# Printing6.net
KiCad netlist of a schematic drawn in Altium Designer
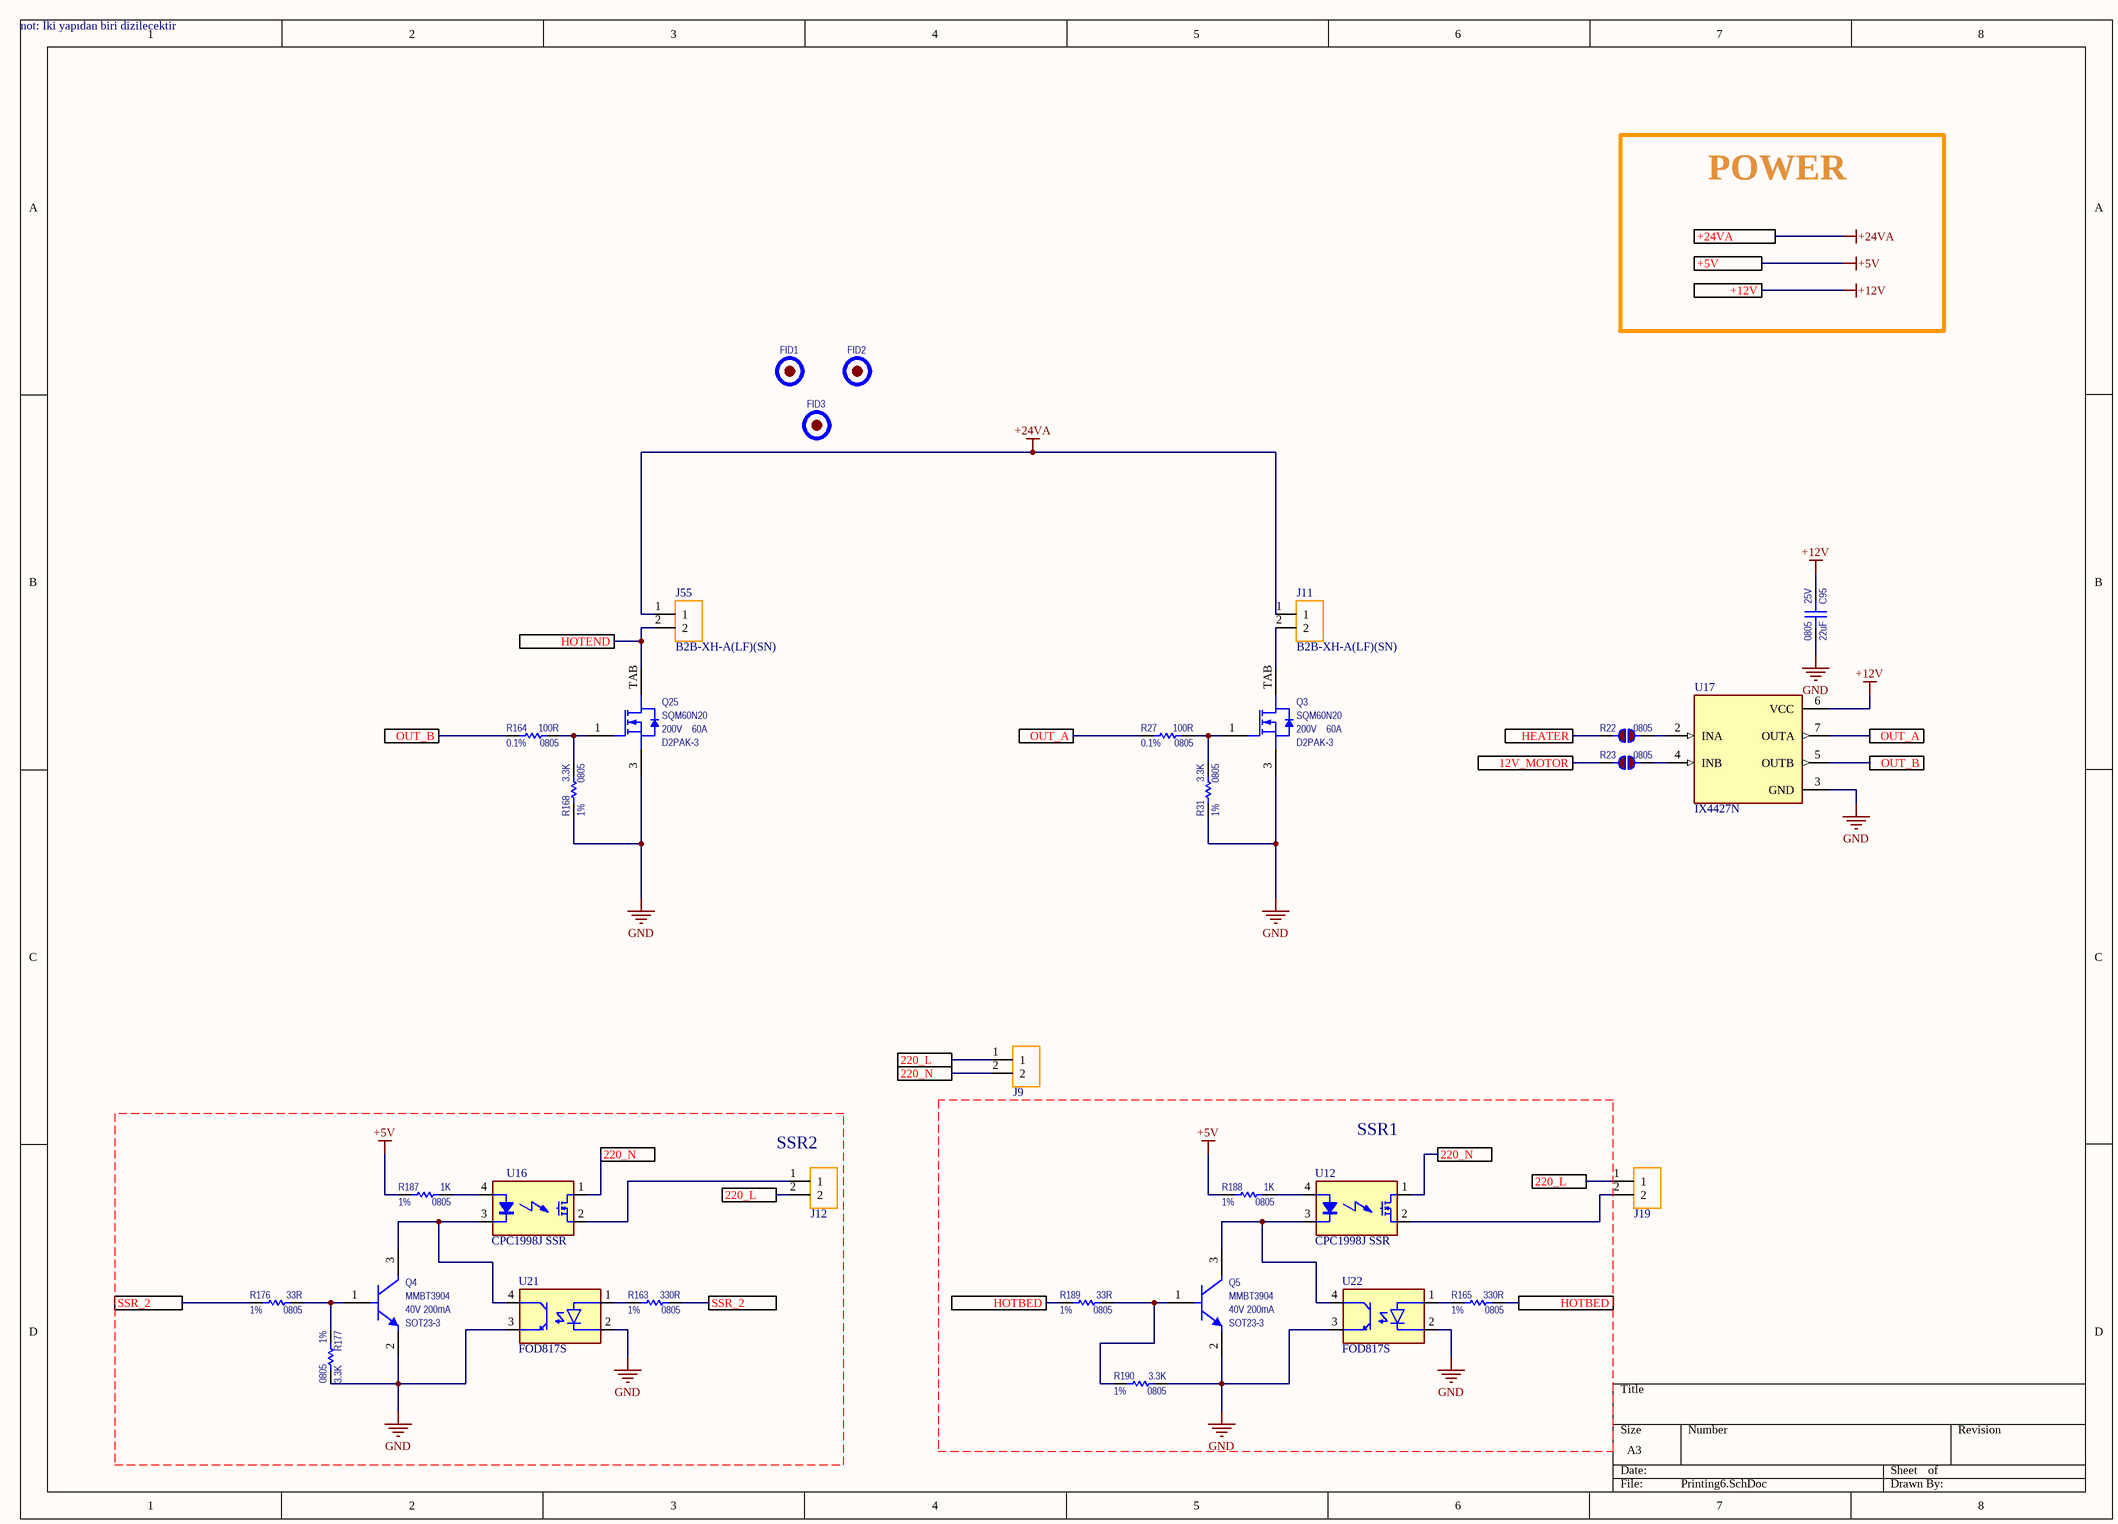
[diagram p0: Printing6.SchDoc]

(export (version "E")
  (design (tool "Eeschema 10.0.6"))
  (components
    (comp (ref "C95")
      (value "22uF")
      (footprint "C_0805_GEN_1.40H")
      (description "CAP_CER_22uF_25V_X5R_20%_0805")
      (fields
        (field (name "VOLTAGE") "25V")
        (field (name "PACKAGE") "0805")
        (field (name "SIMILAR PART") "GRT21BR61E226ME13L; C2012X5R1V226M125AC")
        (field (name "TOLERANCE") "20%")
        (field (name "ADDED BY") "HasanA")
        (field (name "CHECKED BY") "İlkerU")
      )
      (libsource (lib "FireANTs_HwLibDB") (part "Capacitor"))
    )
    (comp (ref "FID1")
      (value "Fiducial_1.00x3.00")
      (footprint "SMD_1.00x3.00_FID")
      (description "SUP_FID_1.00x3.00_SMD")
      (fields
        (field (name "SIMILAR PART") "X")
        (field (name "ADDED BY") "İlhanT")
        (field (name "CHECKED BY") "HasanA")
      )
      (libsource (lib "FireANTs_HwLibDB") (part "Fiducial_1.00x3.00"))
    )
    (comp (ref "FID2")
      (value "Fiducial_1.00x3.00")
      (footprint "SMD_1.00x3.00_FID")
      (description "SUP_FID_1.00x3.00_SMD")
      (fields
        (field (name "SIMILAR PART") "X")
        (field (name "ADDED BY") "İlhanT")
        (field (name "CHECKED BY") "HasanA")
      )
      (libsource (lib "FireANTs_HwLibDB") (part "Fiducial_1.00x3.00"))
    )
    (comp (ref "FID3")
      (value "Fiducial_1.00x3.00")
      (footprint "SMD_1.00x3.00_FID")
      (description "SUP_FID_1.00x3.00_SMD")
      (fields
        (field (name "SIMILAR PART") "X")
        (field (name "ADDED BY") "İlhanT")
        (field (name "CHECKED BY") "HasanA")
      )
      (libsource (lib "FireANTs_HwLibDB") (part "Fiducial_1.00x3.00"))
    )
    (comp (ref "J9")
      (value "5.08 Klemens")
      (footprint "5.08 Klemens")
      (libsource (lib "Printing") (part "5.08 Klemens"))
    )
    (comp (ref "J11")
      (value "B2B-XH-A(LF)(SN)")
      (footprint "JST_B2B-XH-A(LF)(SN)")
      (description "Connector Header Through Hole 2 position 0.098 (2.50mm)")
      (fields (field (name "MF") "JST Sales"))
      (libsource (lib "Printing") (part "B2B-XH-A(LF)(SN)"))
    )
    (comp (ref "J12")
      (value "5.08 Klemens")
      (footprint "5.08 Klemens")
      (libsource (lib "Printing") (part "5.08 Klemens"))
    )
    (comp (ref "J19")
      (value "5.08 Klemens")
      (footprint "5.08 Klemens")
      (libsource (lib "Printing") (part "5.08 Klemens"))
    )
    (comp (ref "J55")
      (value "B2B-XH-A(LF)(SN)")
      (footprint "JST_B2B-XH-A(LF)(SN)")
      (description "Connector Header Through Hole 2 position 0.098 (2.50mm)")
      (fields (field (name "MF") "JST Sales"))
      (libsource (lib "Printing") (part "B2B-XH-A(LF)(SN)"))
    )
    (comp (ref "Q3")
      (value "SQM60N20")
      (footprint "D2PAK-3_SQM60N20-35")
      (description "TRA_NMOS_SING_200V_60A_TH3V_DPAK")
      (fields
        (field (name "CURRENT") "60A")
        (field (name "VOLTAGE") "200V")
        (field (name "PACKAGE") "D2PAK-3")
        (field (name "SIMILAR PART") "SQM10250E_GE3")
        (field (name "TOLERANCE") "X")
        (field (name "ADDED BY") "İlhanT")
        (field (name "CHECKED BY") "EserC")
      )
      (libsource (lib "FireANTs_HwLibDB") (part "SingleNMOS_G1S3DTAB"))
    )
    (comp (ref "Q4")
      (value "MMBT3904")
      (footprint "SOT23-3_MMBT3904,215")
      (description "TRA_NPN_SING_40V_200mA_VSAT300mV_SOT23-3")
      (fields
        (field (name "CURRENT") "200mA")
        (field (name "VOLTAGE") "40V")
        (field (name "PACKAGE") "SOT23-3")
        (field (name "SIMILAR PART") "SST3904HZGT116; PMBT3904,235")
        (field (name "TOLERANCE") "X")
        (field (name "ADDED BY") "HasanA")
        (field (name "CHECKED BY") "EserC")
      )
      (libsource (lib "FireANTs_HwLibDB") (part "SingleNPN_B1E2C3"))
    )
    (comp (ref "Q5")
      (value "MMBT3904")
      (footprint "SOT23-3_MMBT3904,215")
      (description "TRA_NPN_SING_40V_200mA_VSAT300mV_SOT23-3")
      (fields
        (field (name "CURRENT") "200mA")
        (field (name "VOLTAGE") "40V")
        (field (name "PACKAGE") "SOT23-3")
        (field (name "SIMILAR PART") "SST3904HZGT116; PMBT3904,235")
        (field (name "TOLERANCE") "X")
        (field (name "ADDED BY") "HasanA")
        (field (name "CHECKED BY") "EserC")
      )
      (libsource (lib "FireANTs_HwLibDB") (part "SingleNPN_B1E2C3"))
    )
    (comp (ref "Q25")
      (value "SQM60N20")
      (footprint "D2PAK-3_SQM60N20-35")
      (description "TRA_NMOS_SING_200V_60A_TH3V_DPAK")
      (fields
        (field (name "CURRENT") "60A")
        (field (name "VOLTAGE") "200V")
        (field (name "PACKAGE") "D2PAK-3")
        (field (name "SIMILAR PART") "SQM10250E_GE3")
        (field (name "TOLERANCE") "X")
        (field (name "ADDED BY") "İlhanT")
        (field (name "CHECKED BY") "EserC")
      )
      (libsource (lib "FireANTs_HwLibDB") (part "SingleNMOS_G1S3DTAB"))
    )
    (comp (ref "R22")
      (value "StandardJumper")
      (footprint "R_0805_GEN_0.70H")
      (description "RES_STD_0R_0.125W_0805")
      (fields
        (field (name "PACKAGE") "0805")
        (field (name "TOLERANCE") "5%")
        (field (name "VOLTAGE") "150V")
        (field (name "ADDED BY") "İlhanT")
        (field (name "CHECKED BY") "YasinY")
      )
      (libsource (lib "FireANTs_HwLibDB") (part "StandardJumper"))
    )
    (comp (ref "R23")
      (value "StandardJumper")
      (footprint "R_0805_GEN_0.70H")
      (description "RES_STD_0R_0.125W_0805")
      (fields
        (field (name "PACKAGE") "0805")
        (field (name "TOLERANCE") "5%")
        (field (name "VOLTAGE") "150V")
        (field (name "ADDED BY") "İlhanT")
        (field (name "CHECKED BY") "YasinY")
      )
      (libsource (lib "FireANTs_HwLibDB") (part "StandardJumper"))
    )
    (comp (ref "R27")
      (value "100R")
      (footprint "R_0805_GEN_0.70H")
      (description "RES_STD_100R_0.125W_0.1%_10ppm_0805")
      (fields
        (field (name "TOLERANCE") "0.1%")
        (field (name "PACKAGE") "0805")
        (field (name "SIMILAR PART") "RNCF0805TKY100R; RG2012N-101-W-T1")
        (field (name "VOLTAGE") "150V")
        (field (name "ADDED BY") "HasanA")
        (field (name "CHECKED BY") "YasinY")
      )
      (libsource (lib "FireANTs_HwLibDB") (part "StandardResistor"))
    )
    (comp (ref "R31")
      (value "3.3K")
      (footprint "R_0805_GEN_0.70H")
      (description "RES_STD_3.3K_0.125W_1%_100ppm_0805")
      (fields
        (field (name "TOLERANCE") "1%")
        (field (name "PACKAGE") "0805")
        (field (name "VOLTAGE") "150V")
        (field (name "Comment") "StandardResistor")
        (field (name "ADDED BY") "HasanA")
        (field (name "CHECKED BY") "YasinY")
      )
      (libsource (lib "FireANTs_HwLibDB") (part "StandardResistor"))
    )
    (comp (ref "R163")
      (value "330R")
      (footprint "R_0805_GEN_0.70H")
      (description "RES_STD_33R_0.125W_1%_100ppm_0805")
      (fields
        (field (name "TOLERANCE") "1%")
        (field (name "PACKAGE") "0805")
        (field (name "VOLTAGE") "150V")
        (field (name "Comment") "StandardResistor")
        (field (name "ADDED BY") "HasanA")
        (field (name "CHECKED BY") "YasinY")
      )
      (libsource (lib "FireANTs_HwLibDB") (part "StandardResistor"))
    )
    (comp (ref "R164")
      (value "100R")
      (footprint "R_0805_GEN_0.70H")
      (description "RES_STD_100R_0.125W_0.1%_10ppm_0805")
      (fields
        (field (name "TOLERANCE") "0.1%")
        (field (name "PACKAGE") "0805")
        (field (name "SIMILAR PART") "RNCF0805TKY100R; RG2012N-101-W-T1")
        (field (name "VOLTAGE") "150V")
        (field (name "ADDED BY") "HasanA")
        (field (name "CHECKED BY") "YasinY")
      )
      (libsource (lib "FireANTs_HwLibDB") (part "StandardResistor"))
    )
    (comp (ref "R165")
      (value "330R")
      (footprint "R_0805_GEN_0.70H")
      (description "RES_STD_33R_0.125W_1%_100ppm_0805")
      (fields
        (field (name "TOLERANCE") "1%")
        (field (name "PACKAGE") "0805")
        (field (name "VOLTAGE") "150V")
        (field (name "Comment") "StandardResistor")
        (field (name "ADDED BY") "HasanA")
        (field (name "CHECKED BY") "YasinY")
      )
      (libsource (lib "FireANTs_HwLibDB") (part "StandardResistor"))
    )
    (comp (ref "R168")
      (value "3.3K")
      (footprint "R_0805_GEN_0.70H")
      (description "RES_STD_3.3K_0.125W_1%_100ppm_0805")
      (fields
        (field (name "TOLERANCE") "1%")
        (field (name "PACKAGE") "0805")
        (field (name "VOLTAGE") "150V")
        (field (name "Comment") "StandardResistor")
        (field (name "ADDED BY") "HasanA")
        (field (name "CHECKED BY") "YasinY")
      )
      (libsource (lib "FireANTs_HwLibDB") (part "StandardResistor"))
    )
    (comp (ref "R176")
      (value "33R")
      (footprint "R_0805_GEN_0.70H")
      (description "RES_STD_33R_0.125W_1%_100ppm_0805")
      (fields
        (field (name "TOLERANCE") "1%")
        (field (name "PACKAGE") "0805")
        (field (name "VOLTAGE") "150V")
        (field (name "Comment") "StandardResistor")
        (field (name "ADDED BY") "HasanA")
        (field (name "CHECKED BY") "YasinY")
      )
      (libsource (lib "FireANTs_HwLibDB") (part "StandardResistor"))
    )
    (comp (ref "R177")
      (value "3.3K")
      (footprint "R_0805_GEN_0.70H")
      (description "RES_STD_3.3K_0.125W_1%_100ppm_0805")
      (fields
        (field (name "TOLERANCE") "1%")
        (field (name "PACKAGE") "0805")
        (field (name "VOLTAGE") "150V")
        (field (name "Comment") "StandardResistor")
        (field (name "ADDED BY") "HasanA")
        (field (name "CHECKED BY") "YasinY")
      )
      (libsource (lib "FireANTs_HwLibDB") (part "StandardResistor"))
    )
    (comp (ref "R187")
      (value "1K")
      (footprint "R_0805_GEN_0.70H")
      (description "RES_STD_3.3K_0.125W_1%_100ppm_0805")
      (fields
        (field (name "TOLERANCE") "1%")
        (field (name "PACKAGE") "0805")
        (field (name "VOLTAGE") "150V")
        (field (name "Comment") "StandardResistor")
        (field (name "ADDED BY") "HasanA")
        (field (name "CHECKED BY") "YasinY")
      )
      (libsource (lib "FireANTs_HwLibDB") (part "StandardResistor"))
    )
    (comp (ref "R188")
      (value "1K")
      (footprint "R_0805_GEN_0.70H")
      (description "RES_STD_3.3K_0.125W_1%_100ppm_0805")
      (fields
        (field (name "TOLERANCE") "1%")
        (field (name "PACKAGE") "0805")
        (field (name "VOLTAGE") "150V")
        (field (name "Comment") "StandardResistor")
        (field (name "ADDED BY") "HasanA")
        (field (name "CHECKED BY") "YasinY")
      )
      (libsource (lib "FireANTs_HwLibDB") (part "StandardResistor"))
    )
    (comp (ref "R189")
      (value "33R")
      (footprint "R_0805_GEN_0.70H")
      (description "RES_STD_33R_0.125W_1%_100ppm_0805")
      (fields
        (field (name "TOLERANCE") "1%")
        (field (name "PACKAGE") "0805")
        (field (name "VOLTAGE") "150V")
        (field (name "Comment") "StandardResistor")
        (field (name "ADDED BY") "HasanA")
        (field (name "CHECKED BY") "YasinY")
      )
      (libsource (lib "FireANTs_HwLibDB") (part "StandardResistor"))
    )
    (comp (ref "R190")
      (value "3.3K")
      (footprint "R_0805_GEN_0.70H")
      (description "RES_STD_3.3K_0.125W_1%_100ppm_0805")
      (fields
        (field (name "TOLERANCE") "1%")
        (field (name "PACKAGE") "0805")
        (field (name "VOLTAGE") "150V")
        (field (name "Comment") "StandardResistor")
        (field (name "ADDED BY") "HasanA")
        (field (name "CHECKED BY") "YasinY")
      )
      (libsource (lib "FireANTs_HwLibDB") (part "StandardResistor"))
    )
    (comp (ref "U12")
      (value "CPC1998J SSR")
      (footprint "I4-PAC")
      (libsource (lib "Printing") (part "CPC1998J"))
    )
    (comp (ref "U16")
      (value "CPC1998J SSR")
      (footprint "I4-PAC")
      (libsource (lib "Printing") (part "CPC1998J"))
    )
    (comp (ref "U17")
      (value "IX4427N")
      (footprint "SOIC127P600X175-8N")
      (description "Low-Side Gate Driver IC Non-Inverting 8-SOIC")
      (fields (field (name "MF") "IXYS Integrated"))
      (libsource (lib "Printing") (part "IX4427N"))
    )
    (comp (ref "U21")
      (value "FOD817S")
      (footprint "SOIC254P1016X385-4N")
      (description "Optoisolator Transistor Output 5000Vrms 1 Channel 4-SMD")
      (fields (field (name "MF") "ON Semiconductor"))
      (libsource (lib "Printing") (part "FOD817S"))
    )
    (comp (ref "U22")
      (value "FOD817S")
      (footprint "SOIC254P1016X385-4N")
      (description "Optoisolator Transistor Output 5000Vrms 1 Channel 4-SMD")
      (fields (field (name "MF") "ON Semiconductor"))
      (libsource (lib "Printing") (part "FOD817S"))
    )
  )
  (nets
    (net (code "1") (name "+5V") (class "Default")
      (node (ref "R187") (pin "1") (pinfunction "1_1") (pintype "passive"))
      (node (ref "R188") (pin "1") (pinfunction "1_1") (pintype "passive"))
    )
    (net (code "2") (name "+12V") (class "Default")
      (node (ref "C95") (pin "1") (pinfunction "1_1") (pintype "passive"))
      (node (ref "U17") (pin "6") (pinfunction "VCC_6") (pintype "power_in"))
    )
    (net (code "3") (name "+24VA") (class "Default")
      (node (ref "J11") (pin "1") (pinfunction "1_1") (pintype "passive"))
      (node (ref "J55") (pin "1") (pinfunction "1_1") (pintype "passive"))
    )
    (net (code "4") (name "/12V_MOTOR") (class "Default")
      (node (ref "R23") (pin "1") (pinfunction "1_1") (pintype "passive"))
    )
    (net (code "5") (name "/220_L") (class "Default")
      (node (ref "J12") (pin "2") (pinfunction "2_2") (pintype "passive"))
      (node (ref "J19") (pin "1") (pinfunction "1_1") (pintype "passive"))
      (node (ref "J9") (pin "1") (pinfunction "1_1") (pintype "passive"))
    )
    (net (code "6") (name "/220_N") (class "Default")
      (node (ref "J9") (pin "2") (pinfunction "2_2") (pintype "passive"))
      (node (ref "U12") (pin "1") (pinfunction "DS1_1") (pintype "passive"))
      (node (ref "U16") (pin "1") (pinfunction "DS1_1") (pintype "passive"))
    )
    (net (code "7") (name "/HEATER") (class "Default")
      (node (ref "R22") (pin "1") (pinfunction "1_1") (pintype "passive"))
    )
    (net (code "8") (name "/HOTBED") (class "Default")
      (node (ref "R165") (pin "2") (pinfunction "2_2") (pintype "passive"))
      (node (ref "R189") (pin "1") (pinfunction "1_1") (pintype "passive"))
    )
    (net (code "9") (name "/HOTEND") (class "Default")
      (node (ref "J55") (pin "2") (pinfunction "2_2") (pintype "passive"))
      (node (ref "Q25") (pin "TAB") (pinfunction "DRAIN_TAB") (pintype "passive"))
    )
    (net (code "10") (name "/OUT_A") (class "Default")
      (node (ref "R27") (pin "1") (pinfunction "1_1") (pintype "passive"))
      (node (ref "U17") (pin "7") (pinfunction "OUTA_7") (pintype "output"))
    )
    (net (code "11") (name "/OUT_B") (class "Default")
      (node (ref "R164") (pin "1") (pinfunction "1_1") (pintype "passive"))
      (node (ref "U17") (pin "5") (pinfunction "OUTB_5") (pintype "output"))
    )
    (net (code "12") (name "/SSR_2") (class "Default")
      (node (ref "R163") (pin "2") (pinfunction "2_2") (pintype "passive"))
      (node (ref "R176") (pin "1") (pinfunction "1_1") (pintype "passive"))
    )
    (net (code "13") (name "GND") (class "Default")
      (node (ref "C95") (pin "2") (pinfunction "2_2") (pintype "passive"))
      (node (ref "Q25") (pin "3") (pinfunction "SOURCE_3") (pintype "passive"))
      (node (ref "Q3") (pin "3") (pinfunction "SOURCE_3") (pintype "passive"))
      (node (ref "Q4") (pin "2") (pinfunction "EMITTER_2") (pintype "passive"))
      (node (ref "Q5") (pin "2") (pinfunction "EMITTER_2") (pintype "passive"))
      (node (ref "R168") (pin "1") (pinfunction "1_1") (pintype "passive"))
      (node (ref "R177") (pin "2") (pinfunction "2_2") (pintype "passive"))
      (node (ref "R190") (pin "2") (pinfunction "2_2") (pintype "passive"))
      (node (ref "R31") (pin "1") (pinfunction "1_1") (pintype "passive"))
      (node (ref "U17") (pin "3") (pinfunction "GND_3") (pintype "power_in"))
      (node (ref "U21") (pin "2") (pinfunction "CATHODE_2") (pintype "passive"))
      (node (ref "U21") (pin "3") (pinfunction "EMITTER_3") (pintype "passive"))
      (node (ref "U22") (pin "2") (pinfunction "CATHODE_2") (pintype "passive"))
      (node (ref "U22") (pin "3") (pinfunction "EMITTER_3") (pintype "passive"))
    )
    (net (code "14") (name "Net-(Q3-DRAIN)") (class "Default")
      (node (ref "J11") (pin "2") (pinfunction "2_2") (pintype "passive"))
      (node (ref "Q3") (pin "TAB") (pinfunction "DRAIN_TAB") (pintype "passive"))
    )
    (net (code "15") (name "Net-(Q3-GATE)") (class "Default")
      (node (ref "Q3") (pin "1") (pinfunction "GATE_1") (pintype "passive"))
      (node (ref "R27") (pin "2") (pinfunction "2_2") (pintype "passive"))
      (node (ref "R31") (pin "2") (pinfunction "2_2") (pintype "passive"))
    )
    (net (code "16") (name "Net-(Q4-BASE)") (class "Default")
      (node (ref "Q4") (pin "1") (pinfunction "BASE_1") (pintype "passive"))
      (node (ref "R176") (pin "2") (pinfunction "2_2") (pintype "passive"))
      (node (ref "R177") (pin "1") (pinfunction "1_1") (pintype "passive"))
    )
    (net (code "17") (name "Net-(Q4-COLLECTOR)") (class "Default")
      (node (ref "Q4") (pin "3") (pinfunction "COLLECTOR_3") (pintype "passive"))
      (node (ref "U16") (pin "3") (pinfunction "K_3") (pintype "passive"))
      (node (ref "U21") (pin "4") (pinfunction "COLLECTOR_4") (pintype "passive"))
    )
    (net (code "18") (name "Net-(Q5-BASE)") (class "Default")
      (node (ref "Q5") (pin "1") (pinfunction "BASE_1") (pintype "passive"))
      (node (ref "R189") (pin "2") (pinfunction "2_2") (pintype "passive"))
      (node (ref "R190") (pin "1") (pinfunction "1_1") (pintype "passive"))
    )
    (net (code "19") (name "Net-(Q5-COLLECTOR)") (class "Default")
      (node (ref "Q5") (pin "3") (pinfunction "COLLECTOR_3") (pintype "passive"))
      (node (ref "U12") (pin "3") (pinfunction "K_3") (pintype "passive"))
      (node (ref "U22") (pin "4") (pinfunction "COLLECTOR_4") (pintype "passive"))
    )
    (net (code "20") (name "Net-(Q25-GATE)") (class "Default")
      (node (ref "Q25") (pin "1") (pinfunction "GATE_1") (pintype "passive"))
      (node (ref "R164") (pin "2") (pinfunction "2_2") (pintype "passive"))
      (node (ref "R168") (pin "2") (pinfunction "2_2") (pintype "passive"))
    )
    (net (code "21") (name "Net-(U12-A)") (class "Default")
      (node (ref "R188") (pin "2") (pinfunction "2_2") (pintype "passive"))
      (node (ref "U12") (pin "4") (pinfunction "A_4") (pintype "passive"))
    )
    (net (code "22") (name "Net-(U12-DS2)") (class "Default")
      (node (ref "J19") (pin "2") (pinfunction "2_2") (pintype "passive"))
      (node (ref "U12") (pin "2") (pinfunction "DS2_2") (pintype "passive"))
    )
    (net (code "23") (name "Net-(U16-A)") (class "Default")
      (node (ref "R187") (pin "2") (pinfunction "2_2") (pintype "passive"))
      (node (ref "U16") (pin "4") (pinfunction "A_4") (pintype "passive"))
    )
    (net (code "24") (name "Net-(U16-DS2)") (class "Default")
      (node (ref "J12") (pin "1") (pinfunction "1_1") (pintype "passive"))
      (node (ref "U16") (pin "2") (pinfunction "DS2_2") (pintype "passive"))
    )
    (net (code "25") (name "Net-(U17-INA)") (class "Default")
      (node (ref "R22") (pin "2") (pinfunction "2_2") (pintype "passive"))
      (node (ref "U17") (pin "2") (pinfunction "INA_2") (pintype "input"))
    )
    (net (code "26") (name "Net-(U17-INB)") (class "Default")
      (node (ref "R23") (pin "2") (pinfunction "2_2") (pintype "passive"))
      (node (ref "U17") (pin "4") (pinfunction "INB_4") (pintype "input"))
    )
    (net (code "27") (name "Net-(U21-ANODE)") (class "Default")
      (node (ref "R163") (pin "1") (pinfunction "1_1") (pintype "passive"))
      (node (ref "U21") (pin "1") (pinfunction "ANODE_1") (pintype "passive"))
    )
    (net (code "28") (name "Net-(U22-ANODE)") (class "Default")
      (node (ref "R165") (pin "1") (pinfunction "1_1") (pintype "passive"))
      (node (ref "U22") (pin "1") (pinfunction "ANODE_1") (pintype "passive"))
    )
  )
)
